# external_strip_v3_1.net
KiCad netlist of a schematic drawn in EAGLE
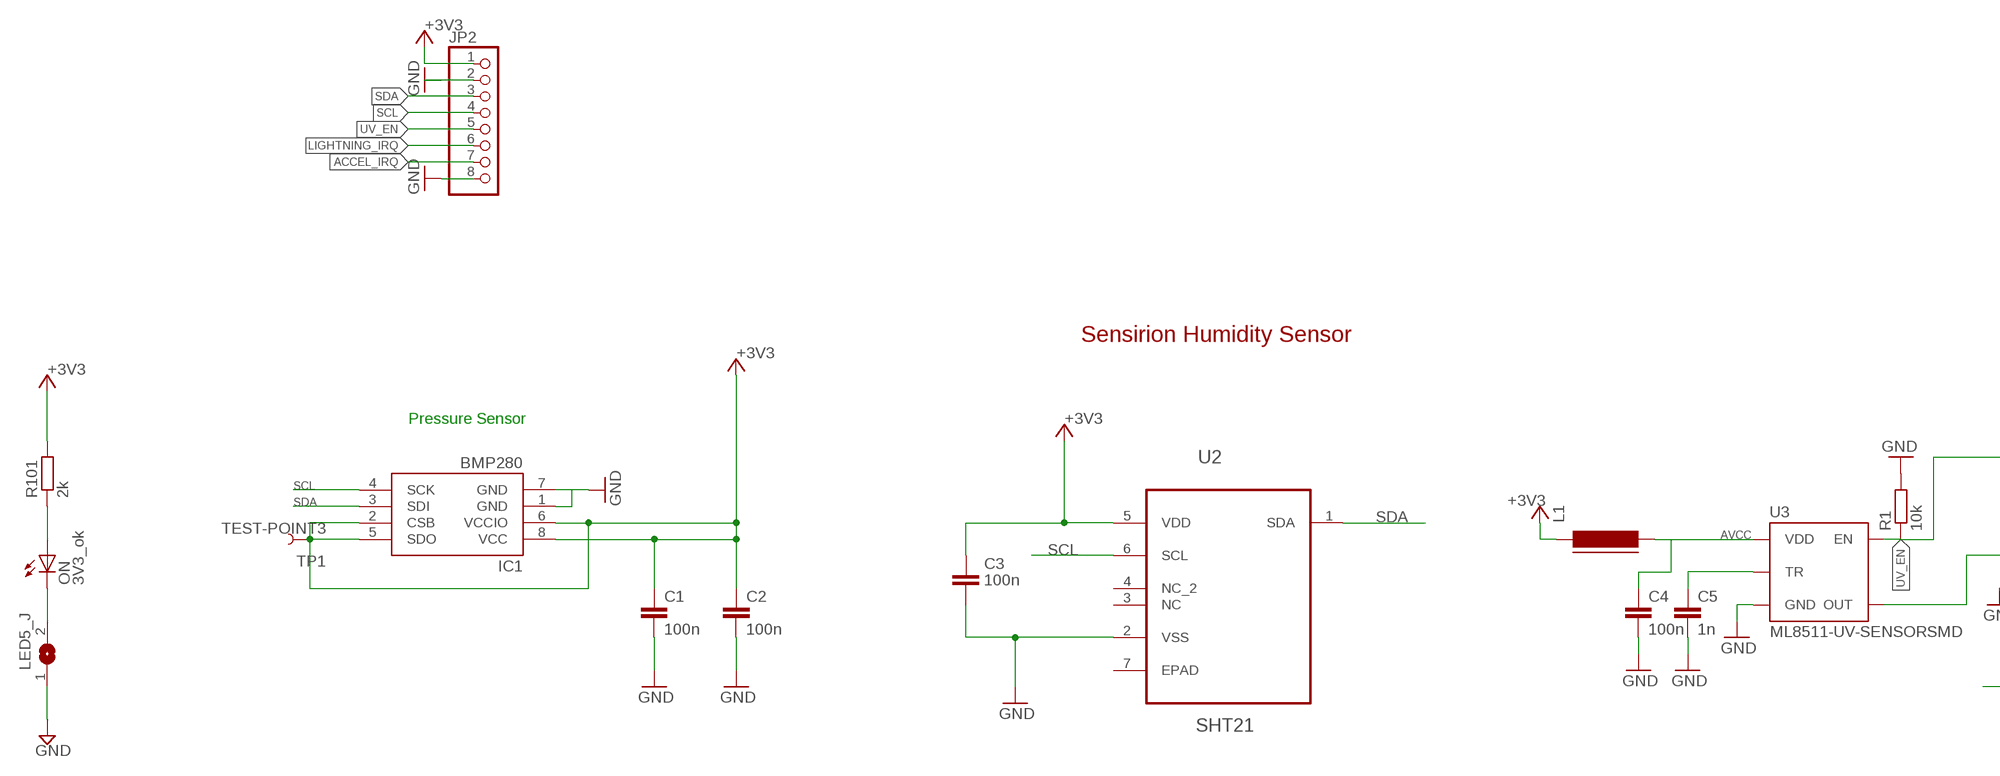
[diagram p0: schematic, sheet 1, part 1 of 2]
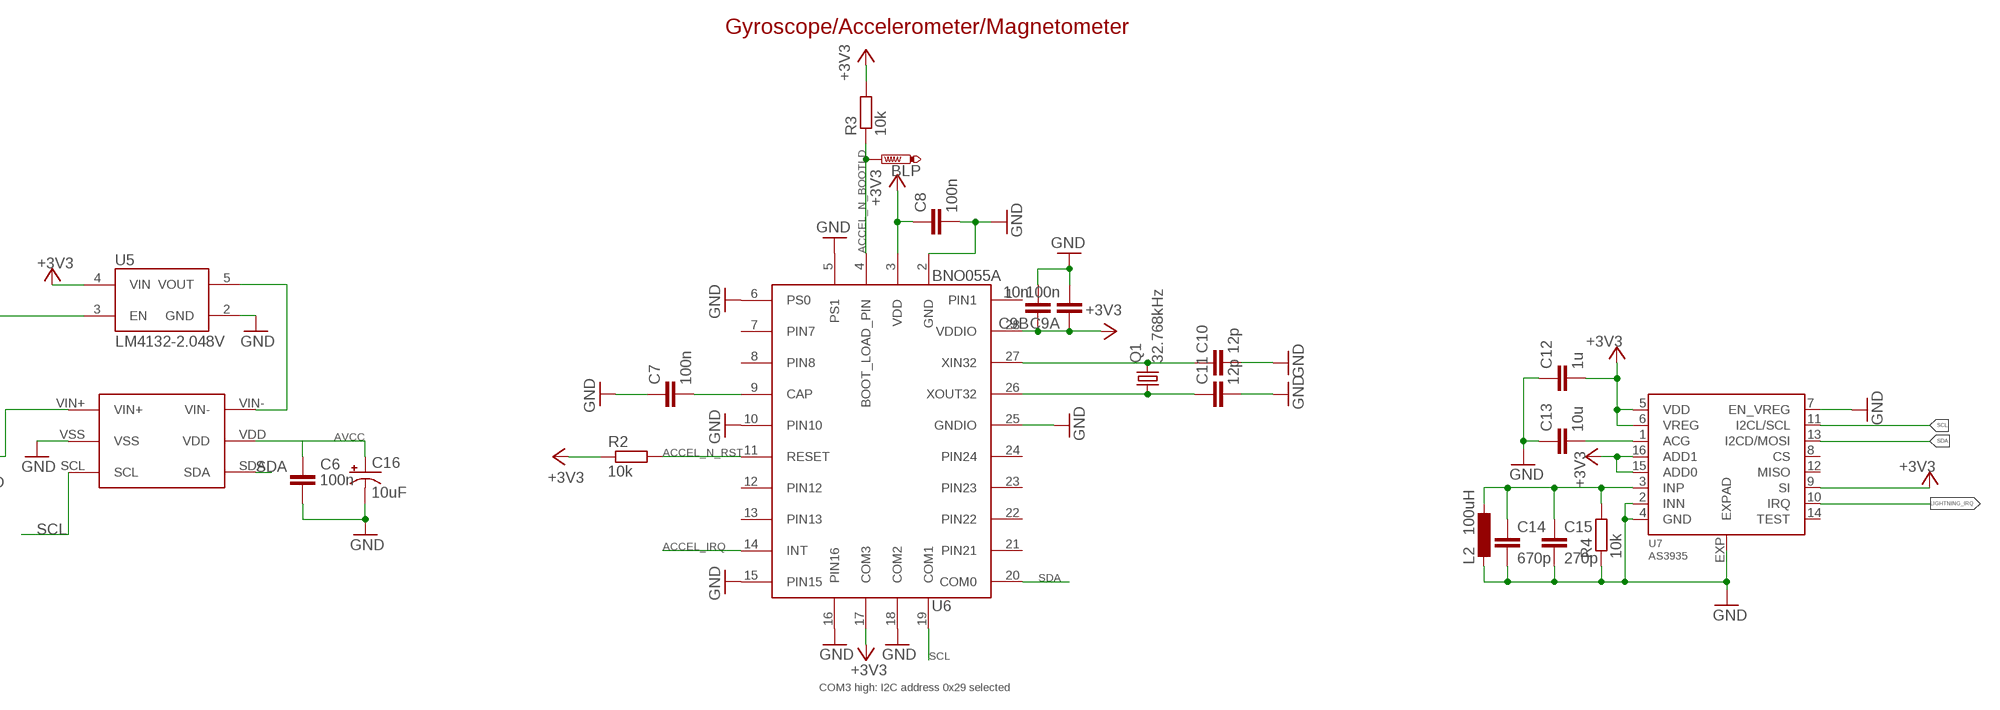
[diagram p1: schematic, sheet 1, part 2 of 2]

(export (version "E")
  (design (tool "Eeschema 10.0.6"))
  (components
    (comp (ref "BLP")
      (value "PTR1B1,27")
      (footprint "eagle-import:B1,27")
      (libsource (lib "eagle-import") (part "PTR1B1,27"))
    )
    (comp (ref "C1")
      (value "100n")
      (footprint "eagle-import:C0603")
      (libsource (lib "eagle-import") (part "C-EUC0603"))
    )
    (comp (ref "C2")
      (value "100n")
      (footprint "eagle-import:C0603")
      (libsource (lib "eagle-import") (part "C-EUC0603"))
    )
    (comp (ref "C3")
      (value "100n")
      (footprint "eagle-import:C0603")
      (libsource (lib "eagle-import") (part "C-EUC0603"))
    )
    (comp (ref "C4")
      (value "100n")
      (footprint "eagle-import:0603-CAP")
      (libsource (lib "eagle-import") (part "0.1UF-25V(+80/-20%)(0603)"))
    )
    (comp (ref "C5")
      (value "1n")
      (footprint "eagle-import:0603-CAP")
      (libsource (lib "eagle-import") (part "1NF/1000PF-50V-10%(0603)"))
    )
    (comp (ref "C6")
      (value "100n")
      (footprint "eagle-import:C0603")
      (libsource (lib "eagle-import") (part "C-EUC0603"))
    )
    (comp (ref "C7")
      (value "100n")
      (footprint "eagle-import:C0603")
      (libsource (lib "eagle-import") (part "C-EUC0603"))
    )
    (comp (ref "C8")
      (value "100n")
      (footprint "eagle-import:C0603")
      (libsource (lib "eagle-import") (part "C-EUC0603"))
    )
    (comp (ref "C9A")
      (value "100n")
      (footprint "eagle-import:C0603")
      (libsource (lib "eagle-import") (part "C-EUC0603"))
    )
    (comp (ref "C9B")
      (value "10n")
      (footprint "eagle-import:C0603")
      (libsource (lib "eagle-import") (part "C-EUC0603"))
    )
    (comp (ref "C10")
      (value "12p")
      (footprint "eagle-import:C0603")
      (libsource (lib "eagle-import") (part "C-EUC0603"))
    )
    (comp (ref "C11")
      (value "12p")
      (footprint "eagle-import:C0603")
      (libsource (lib "eagle-import") (part "C-EUC0603"))
    )
    (comp (ref "C12")
      (value "1u")
      (footprint "eagle-import:C0603")
      (libsource (lib "eagle-import") (part "C-EUC0603"))
    )
    (comp (ref "C13")
      (value "10u")
      (footprint "eagle-import:C0603")
      (libsource (lib "eagle-import") (part "C-EUC0603"))
    )
    (comp (ref "C14")
      (value "670p")
      (footprint "eagle-import:C0603")
      (libsource (lib "eagle-import") (part "C-EUC0603"))
    )
    (comp (ref "C15")
      (value "270p")
      (footprint "eagle-import:C0603")
      (libsource (lib "eagle-import") (part "C-EUC0603"))
    )
    (comp (ref "C16")
      (value "10uF")
      (footprint "eagle-import:EIA3216")
      (libsource (lib "eagle-import") (part "10UF-TANT"))
    )
    (comp (ref "IC1")
      (value "BMP280")
      (footprint "eagle-import:LGA8")
      (libsource (lib "eagle-import") (part "BMP280"))
    )
    (comp (ref "JP2")
      (value "PINHD-1X8")
      (footprint "eagle-import:1X08")
      (libsource (lib "eagle-import") (part "PINHD-1X8"))
    )
    (comp (ref "L1")
      (value "FERRITE-0603")
      (footprint "eagle-import:FB603")
      (libsource (lib "eagle-import") (part "FERRITE-0603"))
    )
    (comp (ref "L2")
      (value "100uH")
      (footprint "eagle-import:COILCRAFT")
      (libsource (lib "eagle-import") (part "COILCRAFT"))
    )
    (comp (ref "LED5_J")
      (value "SJ")
      (footprint "eagle-import:SJ")
      (libsource (lib "eagle-import") (part "SJ"))
    )
    (comp (ref "ON")
      (value "3V3_ok")
      (footprint "eagle-import:CHIPLED_0603")
      (libsource (lib "eagle-import") (part "LEDCHIPLED_0603"))
    )
    (comp (ref "Q1")
      (value "32.768kHz")
      (footprint "eagle-import:FC-12M")
      (libsource (lib "eagle-import") (part "FC-12M"))
    )
    (comp (ref "R1")
      (value "10k")
      (footprint "eagle-import:R0603")
      (libsource (lib "eagle-import") (part "resistor_R-EU_R0603"))
    )
    (comp (ref "R2")
      (value "10k")
      (footprint "eagle-import:R0603")
      (libsource (lib "eagle-import") (part "R-EU_R0603"))
    )
    (comp (ref "R3")
      (value "10k")
      (footprint "eagle-import:R0603")
      (libsource (lib "eagle-import") (part "R-EU_R0603"))
    )
    (comp (ref "R4")
      (value "10k")
      (footprint "eagle-import:R0603")
      (libsource (lib "eagle-import") (part "resistor_R-EU_R0603"))
    )
    (comp (ref "R101")
      (value "2k")
      (footprint "eagle-import:R0603")
      (libsource (lib "eagle-import") (part "R-EU_R0603"))
    )
    (comp (ref "TP1")
      (value "TEST-POINT3")
      (footprint "eagle-import:PAD.03X.03")
      (libsource (lib "eagle-import") (part "TEST-POINT3"))
    )
    (comp (ref "U2")
      (value "SHT21")
      (footprint "eagle-import:DFN300X300X110-7N")
      (libsource (lib "eagle-import") (part "SHT21"))
    )
    (comp (ref "U3")
      (value "ML8511-UV-SENSORSMD")
      (footprint "eagle-import:ML8511")
      (libsource (lib "eagle-import") (part "ML8511-UV-SENSORSMD"))
    )
    (comp (ref "U4")
      (value "MCP3425")
      (footprint "eagle-import:SOT-23-6")
      (libsource (lib "eagle-import") (part "MCP3425"))
    )
    (comp (ref "U5")
      (value "LM4132-2.048V")
      (footprint "eagle-import:SOT23-5")
      (libsource (lib "eagle-import") (part "LM4128-2.5VREF"))
    )
    (comp (ref "U6")
      (value "BNO055A")
      (footprint "eagle-import:BNO055")
      (libsource (lib "eagle-import") (part "BNO055A"))
    )
    (comp (ref "U7")
      (value "AS3935")
      (footprint "eagle-import:16LDMLPQ")
      (libsource (lib "eagle-import") (part "AS3935"))
    )
  )
  (nets
    (net (code "1") (name "+3V3") (class "Default")
      (node (ref "C1") (pin "1") (pinfunction "1_1") (pintype "passive"))
      (node (ref "C12") (pin "2") (pinfunction "2_2") (pintype "passive"))
      (node (ref "C2") (pin "1") (pinfunction "1_1") (pintype "passive"))
      (node (ref "C3") (pin "1") (pinfunction "1_1") (pintype "passive"))
      (node (ref "C8") (pin "1") (pinfunction "1_1") (pintype "passive"))
      (node (ref "C9A") (pin "1") (pinfunction "1_1") (pintype "passive"))
      (node (ref "C9B") (pin "1") (pinfunction "1_1") (pintype "passive"))
      (node (ref "IC1") (pin "2") (pinfunction "CSB_2") (pintype "input"))
      (node (ref "IC1") (pin "5") (pinfunction "SDO_5") (pintype "bidirectional"))
      (node (ref "IC1") (pin "6") (pinfunction "VCCIO_6") (pintype "power_in"))
      (node (ref "IC1") (pin "8") (pinfunction "VCC_8") (pintype "power_in"))
      (node (ref "JP2") (pin "1") (pinfunction "1_1") (pintype "passive"))
      (node (ref "L1") (pin "1") (pinfunction "1_1") (pintype "passive"))
      (node (ref "R101") (pin "2") (pinfunction "2_2") (pintype "passive"))
      (node (ref "R2") (pin "1") (pinfunction "1_1") (pintype "passive"))
      (node (ref "R3") (pin "2") (pinfunction "2_2") (pintype "passive"))
      (node (ref "TP1") (pin "P$1") (pinfunction "1_P$1") (pintype "bidirectional"))
      (node (ref "U2") (pin "5") (pinfunction "VDD_5") (pintype "power_in"))
      (node (ref "U5") (pin "4") (pinfunction "VIN_4") (pintype "bidirectional"))
      (node (ref "U6") (pin "17") (pinfunction "COM3_17") (pintype "bidirectional"))
      (node (ref "U6") (pin "28") (pinfunction "VDDIO_28") (pintype "bidirectional"))
      (node (ref "U6") (pin "3") (pinfunction "VDD_3") (pintype "bidirectional"))
      (node (ref "U7") (pin "15") (pinfunction "ADD0_15") (pintype "bidirectional"))
      (node (ref "U7") (pin "16") (pinfunction "ADD1_16") (pintype "bidirectional"))
      (node (ref "U7") (pin "5") (pinfunction "VDD_5") (pintype "bidirectional"))
      (node (ref "U7") (pin "6") (pinfunction "VREG_6") (pintype "bidirectional"))
      (node (ref "U7") (pin "9") (pinfunction "SI_9") (pintype "bidirectional"))
    )
    (net (code "2") (name "/ACCEL_N_BOOTLD") (class "Default")
      (node (ref "BLP") (pin "TP") (pinfunction "TP_TP") (pintype "input"))
      (node (ref "R3") (pin "1") (pinfunction "1_1") (pintype "passive"))
      (node (ref "U6") (pin "4") (pinfunction "BOOT_LOAD_PIN_4") (pintype "bidirectional"))
    )
    (net (code "3") (name "/ACCEL_N_RST") (class "Default")
      (node (ref "R2") (pin "2") (pinfunction "2_2") (pintype "passive"))
      (node (ref "U6") (pin "11") (pinfunction "RESET_11") (pintype "bidirectional"))
    )
    (net (code "4") (name "/AVCC") (class "Default")
      (node (ref "C16") (pin "A") (pinfunction "+_A") (pintype "passive"))
      (node (ref "C4") (pin "1") (pinfunction "1_1") (pintype "passive"))
      (node (ref "C6") (pin "1") (pinfunction "1_1") (pintype "passive"))
      (node (ref "L1") (pin "2") (pinfunction "2_2") (pintype "passive"))
      (node (ref "U3") (pin "7") (pinfunction "VDD_7") (pintype "power_in"))
      (node (ref "U4") (pin "VDD") (pinfunction "VDD_VDD") (pintype "bidirectional"))
    )
    (net (code "5") (name "ACCEL_IRQ") (class "Default")
      (node (ref "JP2") (pin "7") (pinfunction "7_7") (pintype "passive"))
      (node (ref "U6") (pin "14") (pinfunction "INT_14") (pintype "bidirectional"))
    )
    (net (code "6") (name "GND") (class "Default")
      (node (ref "C1") (pin "2") (pinfunction "2_2") (pintype "passive"))
      (node (ref "C10") (pin "2") (pinfunction "2_2") (pintype "passive"))
      (node (ref "C11") (pin "2") (pinfunction "2_2") (pintype "passive"))
      (node (ref "C12") (pin "1") (pinfunction "1_1") (pintype "passive"))
      (node (ref "C13") (pin "1") (pinfunction "1_1") (pintype "passive"))
      (node (ref "C14") (pin "2") (pinfunction "2_2") (pintype "passive"))
      (node (ref "C15") (pin "2") (pinfunction "2_2") (pintype "passive"))
      (node (ref "C16") (pin "C") (pinfunction "-_C") (pintype "passive"))
      (node (ref "C2") (pin "2") (pinfunction "2_2") (pintype "passive"))
      (node (ref "C3") (pin "2") (pinfunction "2_2") (pintype "passive"))
      (node (ref "C4") (pin "2") (pinfunction "2_2") (pintype "passive"))
      (node (ref "C5") (pin "2") (pinfunction "2_2") (pintype "passive"))
      (node (ref "C6") (pin "2") (pinfunction "2_2") (pintype "passive"))
      (node (ref "C7") (pin "1") (pinfunction "1_1") (pintype "passive"))
      (node (ref "C8") (pin "2") (pinfunction "2_2") (pintype "passive"))
      (node (ref "C9A") (pin "2") (pinfunction "2_2") (pintype "passive"))
      (node (ref "C9B") (pin "2") (pinfunction "2_2") (pintype "passive"))
      (node (ref "IC1") (pin "1") (pinfunction "GND_1") (pintype "power_in"))
      (node (ref "IC1") (pin "7") (pinfunction "GND_7") (pintype "power_in"))
      (node (ref "JP2") (pin "2") (pinfunction "2_2") (pintype "passive"))
      (node (ref "JP2") (pin "8") (pinfunction "8_8") (pintype "passive"))
      (node (ref "L2") (pin "2") (pinfunction "2_2") (pintype "passive"))
      (node (ref "LED5_J") (pin "1") (pinfunction "1_1") (pintype "passive"))
      (node (ref "R1") (pin "2") (pinfunction "2_2") (pintype "passive"))
      (node (ref "R4") (pin "1") (pinfunction "1_1") (pintype "passive"))
      (node (ref "U2") (pin "2") (pinfunction "VSS_2") (pintype "power_in"))
      (node (ref "U3") (pin "5") (pinfunction "GND_5") (pintype "power_in"))
      (node (ref "U4") (pin "VSS") (pinfunction "VSS_VSS") (pintype "bidirectional"))
      (node (ref "U5") (pin "2") (pinfunction "GND_2") (pintype "bidirectional"))
      (node (ref "U6") (pin "10") (pinfunction "PIN10_10") (pintype "bidirectional"))
      (node (ref "U6") (pin "15") (pinfunction "PIN15_15") (pintype "bidirectional"))
      (node (ref "U6") (pin "16") (pinfunction "PIN16_16") (pintype "bidirectional"))
      (node (ref "U6") (pin "18") (pinfunction "COM2_18") (pintype "bidirectional"))
      (node (ref "U6") (pin "2") (pinfunction "GND_2") (pintype "bidirectional"))
      (node (ref "U6") (pin "25") (pinfunction "GNDIO_25") (pintype "bidirectional"))
      (node (ref "U6") (pin "5") (pinfunction "PS1_5") (pintype "bidirectional"))
      (node (ref "U6") (pin "6") (pinfunction "PS0_6") (pintype "bidirectional"))
      (node (ref "U7") (pin "2") (pinfunction "INN_2") (pintype "bidirectional"))
      (node (ref "U7") (pin "4") (pinfunction "GND_4") (pintype "bidirectional"))
      (node (ref "U7") (pin "7") (pinfunction "EN_VREG_7") (pintype "bidirectional"))
      (node (ref "U7") (pin "EXP") (pinfunction "EXPAD_EXP") (pintype "bidirectional"))
    )
    (net (code "7") (name "LIGHTNING_IRQ") (class "Default")
      (node (ref "JP2") (pin "6") (pinfunction "6_6") (pintype "passive"))
      (node (ref "U7") (pin "10") (pinfunction "IRQ_10") (pintype "bidirectional"))
    )
    (net (code "8") (name "Net-(LED5_J-Pad2)") (class "Default")
      (node (ref "LED5_J") (pin "2") (pinfunction "2_2") (pintype "passive"))
      (node (ref "ON") (pin "C") (pinfunction "C_C") (pintype "passive"))
    )
    (net (code "9") (name "Net-(ON-PadA)") (class "Default")
      (node (ref "ON") (pin "A") (pinfunction "A_A") (pintype "passive"))
      (node (ref "R101") (pin "1") (pinfunction "1_1") (pintype "passive"))
    )
    (net (code "10") (name "Net-(U3-OUT)") (class "Default")
      (node (ref "U3") (pin "8") (pinfunction "OUT_8") (pintype "output"))
      (node (ref "U4") (pin "VIN+") (pinfunction "VIN+_VIN+") (pintype "bidirectional"))
    )
    (net (code "11") (name "Net-(U3-TR)") (class "Default")
      (node (ref "C5") (pin "1") (pinfunction "1_1") (pintype "passive"))
      (node (ref "U3") (pin "9") (pinfunction "TR_9") (pintype "power_in"))
    )
    (net (code "12") (name "Net-(U5-VOUT)") (class "Default")
      (node (ref "U4") (pin "VIN-") (pinfunction "VIN-_VIN-") (pintype "bidirectional"))
      (node (ref "U5") (pin "5") (pinfunction "VOUT_5") (pintype "bidirectional"))
    )
    (net (code "13") (name "Net-(U6-CAP)") (class "Default")
      (node (ref "C7") (pin "2") (pinfunction "2_2") (pintype "passive"))
      (node (ref "U6") (pin "9") (pinfunction "CAP_9") (pintype "bidirectional"))
    )
    (net (code "14") (name "Net-(U6-XIN32)") (class "Default")
      (node (ref "C10") (pin "1") (pinfunction "1_1") (pintype "passive"))
      (node (ref "Q1") (pin "2") (pinfunction "2_2") (pintype "passive"))
      (node (ref "U6") (pin "27") (pinfunction "XIN32_27") (pintype "bidirectional"))
    )
    (net (code "15") (name "Net-(U6-XOUT32)") (class "Default")
      (node (ref "C11") (pin "1") (pinfunction "1_1") (pintype "passive"))
      (node (ref "Q1") (pin "1") (pinfunction "1_1") (pintype "passive"))
      (node (ref "U6") (pin "26") (pinfunction "XOUT32_26") (pintype "bidirectional"))
    )
    (net (code "16") (name "Net-(U7-ACG)") (class "Default")
      (node (ref "C13") (pin "2") (pinfunction "2_2") (pintype "passive"))
      (node (ref "U7") (pin "1") (pinfunction "ACG_1") (pintype "bidirectional"))
    )
    (net (code "17") (name "Net-(U7-INP)") (class "Default")
      (node (ref "C14") (pin "1") (pinfunction "1_1") (pintype "passive"))
      (node (ref "C15") (pin "1") (pinfunction "1_1") (pintype "passive"))
      (node (ref "L2") (pin "1") (pinfunction "1_1") (pintype "passive"))
      (node (ref "R4") (pin "2") (pinfunction "2_2") (pintype "passive"))
      (node (ref "U7") (pin "3") (pinfunction "INP_3") (pintype "bidirectional"))
    )
    (net (code "18") (name "SCL") (class "Default")
      (node (ref "IC1") (pin "4") (pinfunction "SCK_4") (pintype "bidirectional"))
      (node (ref "JP2") (pin "4") (pinfunction "4_4") (pintype "passive"))
      (node (ref "U2") (pin "6") (pinfunction "SCL_6") (pintype "input"))
      (node (ref "U4") (pin "SCL") (pinfunction "SCL_SCL") (pintype "bidirectional"))
      (node (ref "U6") (pin "19") (pinfunction "COM1_19") (pintype "bidirectional"))
      (node (ref "U7") (pin "11") (pinfunction "I2CL/SCL_11") (pintype "bidirectional"))
    )
    (net (code "19") (name "SDA") (class "Default")
      (node (ref "IC1") (pin "3") (pinfunction "SDI_3") (pintype "bidirectional"))
      (node (ref "JP2") (pin "3") (pinfunction "3_3") (pintype "passive"))
      (node (ref "U2") (pin "1") (pinfunction "SDA_1") (pintype "bidirectional"))
      (node (ref "U4") (pin "SDA") (pinfunction "SDA_SDA") (pintype "bidirectional"))
      (node (ref "U6") (pin "20") (pinfunction "COM0_20") (pintype "bidirectional"))
      (node (ref "U7") (pin "13") (pinfunction "I2CD/MOSI_13") (pintype "bidirectional"))
    )
    (net (code "20") (name "UV_EN") (class "Default")
      (node (ref "JP2") (pin "5") (pinfunction "5_5") (pintype "passive"))
      (node (ref "R1") (pin "1") (pinfunction "1_1") (pintype "passive"))
      (node (ref "U3") (pin "4") (pinfunction "EN_4") (pintype "input"))
      (node (ref "U5") (pin "3") (pinfunction "EN_3") (pintype "bidirectional"))
    )
    (net (code "21") (name "unconnected-(U2-EPAD-Pad7)") (class "Default")
      (node (ref "U2") (pin "7") (pinfunction "EPAD_7") (pintype "passive"))
    )
    (net (code "22") (name "unconnected-(U2-NC-Pad3)") (class "Default")
      (node (ref "U2") (pin "3") (pinfunction "NC_3") (pintype "no_connect"))
    )
    (net (code "23") (name "unconnected-(U2-NC_2-Pad4)") (class "Default")
      (node (ref "U2") (pin "4") (pinfunction "NC_2_4") (pintype "no_connect"))
    )
    (net (code "24") (name "unconnected-(U6-PIN1-Pad1)") (class "Default")
      (node (ref "U6") (pin "1") (pinfunction "PIN1_1") (pintype "bidirectional"))
    )
    (net (code "25") (name "unconnected-(U6-PIN7-Pad7)") (class "Default")
      (node (ref "U6") (pin "7") (pinfunction "PIN7_7") (pintype "bidirectional"))
    )
    (net (code "26") (name "unconnected-(U6-PIN8-Pad8)") (class "Default")
      (node (ref "U6") (pin "8") (pinfunction "PIN8_8") (pintype "bidirectional"))
    )
    (net (code "27") (name "unconnected-(U6-PIN12-Pad12)") (class "Default")
      (node (ref "U6") (pin "12") (pinfunction "PIN12_12") (pintype "bidirectional"))
    )
    (net (code "28") (name "unconnected-(U6-PIN13-Pad13)") (class "Default")
      (node (ref "U6") (pin "13") (pinfunction "PIN13_13") (pintype "bidirectional"))
    )
    (net (code "29") (name "unconnected-(U6-PIN21-Pad21)") (class "Default")
      (node (ref "U6") (pin "21") (pinfunction "PIN21_21") (pintype "bidirectional"))
    )
    (net (code "30") (name "unconnected-(U6-PIN22-Pad22)") (class "Default")
      (node (ref "U6") (pin "22") (pinfunction "PIN22_22") (pintype "bidirectional"))
    )
    (net (code "31") (name "unconnected-(U6-PIN23-Pad23)") (class "Default")
      (node (ref "U6") (pin "23") (pinfunction "PIN23_23") (pintype "bidirectional"))
    )
    (net (code "32") (name "unconnected-(U6-PIN24-Pad24)") (class "Default")
      (node (ref "U6") (pin "24") (pinfunction "PIN24_24") (pintype "bidirectional"))
    )
    (net (code "33") (name "unconnected-(U7-CS-Pad8)") (class "Default")
      (node (ref "U7") (pin "8") (pinfunction "CS_8") (pintype "bidirectional"))
    )
    (net (code "34") (name "unconnected-(U7-MISO-Pad12)") (class "Default")
      (node (ref "U7") (pin "12") (pinfunction "MISO_12") (pintype "bidirectional"))
    )
    (net (code "35") (name "unconnected-(U7-TEST-Pad14)") (class "Default")
      (node (ref "U7") (pin "14") (pinfunction "TEST_14") (pintype "passive"))
    )
  )
)
